# proto.net
KiCad netlist of a schematic drawn in EAGLE
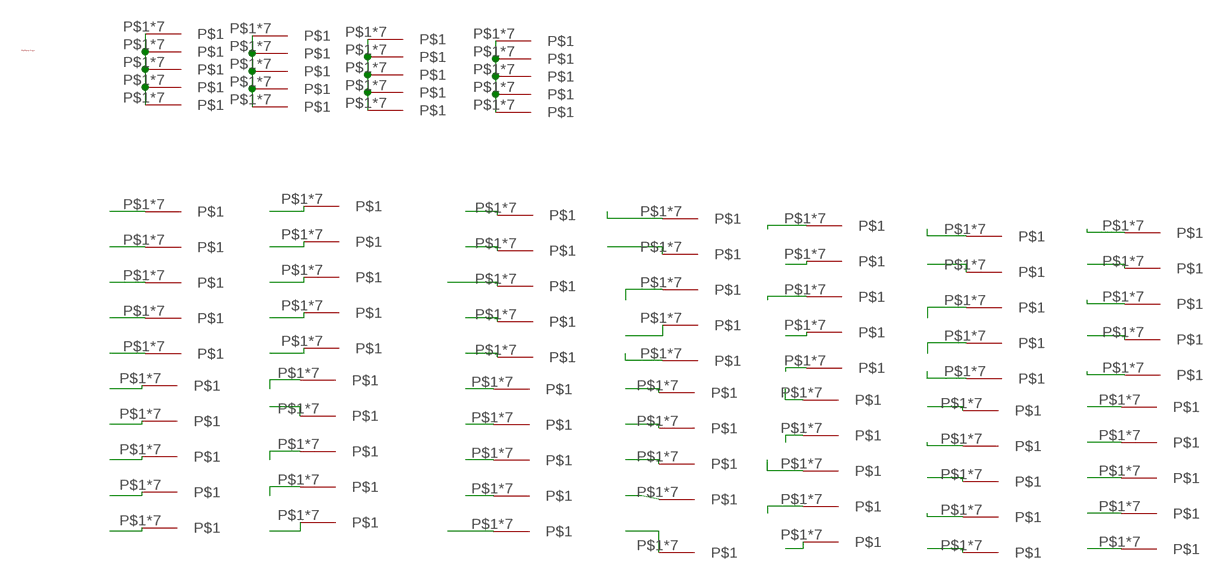
[diagram p0: schematic, sheet 1]

(export (version "E")
  (design (tool "Eeschema 10.0.6"))
  (components
    (comp (ref "U$1")
      (value "LOGO_HACKHEIM")
      (footprint "eagle-import:LOGO_HACKHEIM")
      (libsource (lib "eagle-import") (part "LOGO_HACKHEIM"))
    )
    (comp (ref "U$4")
      (value "PROTO_PAD")
      (footprint "eagle-import:PROTO_PAD")
      (libsource (lib "eagle-import") (part "PROTO_PAD"))
    )
    (comp (ref "U$5")
      (value "PROTO_PAD")
      (footprint "eagle-import:PROTO_PAD")
      (libsource (lib "eagle-import") (part "PROTO_PAD"))
    )
    (comp (ref "U$6")
      (value "PROTO_PAD")
      (footprint "eagle-import:PROTO_PAD")
      (libsource (lib "eagle-import") (part "PROTO_PAD"))
    )
    (comp (ref "U$7")
      (value "PROTO_PAD")
      (footprint "eagle-import:PROTO_PAD")
      (libsource (lib "eagle-import") (part "PROTO_PAD"))
    )
    (comp (ref "U$8")
      (value "PROTO_PAD")
      (footprint "eagle-import:PROTO_PAD")
      (libsource (lib "eagle-import") (part "PROTO_PAD"))
    )
    (comp (ref "U$9")
      (value "PROTO_PAD")
      (footprint "eagle-import:PROTO_PAD")
      (libsource (lib "eagle-import") (part "PROTO_PAD"))
    )
    (comp (ref "U$10")
      (value "PROTO_PAD")
      (footprint "eagle-import:PROTO_PAD")
      (libsource (lib "eagle-import") (part "PROTO_PAD"))
    )
    (comp (ref "U$11")
      (value "PROTO_PAD")
      (footprint "eagle-import:PROTO_PAD")
      (libsource (lib "eagle-import") (part "PROTO_PAD"))
    )
    (comp (ref "U$12")
      (value "PROTO_PAD")
      (footprint "eagle-import:PROTO_PAD")
      (libsource (lib "eagle-import") (part "PROTO_PAD"))
    )
    (comp (ref "U$13")
      (value "PROTO_PAD")
      (footprint "eagle-import:PROTO_PAD")
      (libsource (lib "eagle-import") (part "PROTO_PAD"))
    )
    (comp (ref "U$14")
      (value "PROTO_PAD")
      (footprint "eagle-import:PROTO_PAD")
      (libsource (lib "eagle-import") (part "PROTO_PAD"))
    )
    (comp (ref "U$15")
      (value "PROTO_PAD")
      (footprint "eagle-import:PROTO_PAD")
      (libsource (lib "eagle-import") (part "PROTO_PAD"))
    )
    (comp (ref "U$16")
      (value "PROTO_PAD")
      (footprint "eagle-import:PROTO_PAD")
      (libsource (lib "eagle-import") (part "PROTO_PAD"))
    )
    (comp (ref "U$17")
      (value "PROTO_PAD")
      (footprint "eagle-import:PROTO_PAD")
      (libsource (lib "eagle-import") (part "PROTO_PAD"))
    )
    (comp (ref "U$18")
      (value "PROTO_PAD")
      (footprint "eagle-import:PROTO_PAD")
      (libsource (lib "eagle-import") (part "PROTO_PAD"))
    )
    (comp (ref "U$19")
      (value "PROTO_PAD")
      (footprint "eagle-import:PROTO_PAD")
      (libsource (lib "eagle-import") (part "PROTO_PAD"))
    )
    (comp (ref "U$20")
      (value "PROTO_PAD")
      (footprint "eagle-import:PROTO_PAD")
      (libsource (lib "eagle-import") (part "PROTO_PAD"))
    )
    (comp (ref "U$21")
      (value "PROTO_PAD")
      (footprint "eagle-import:PROTO_PAD")
      (libsource (lib "eagle-import") (part "PROTO_PAD"))
    )
    (comp (ref "U$22")
      (value "PROTO_PAD")
      (footprint "eagle-import:PROTO_PAD")
      (libsource (lib "eagle-import") (part "PROTO_PAD"))
    )
    (comp (ref "U$23")
      (value "PROTO_PAD")
      (footprint "eagle-import:PROTO_PAD")
      (libsource (lib "eagle-import") (part "PROTO_PAD"))
    )
    (comp (ref "U$24")
      (value "PROTO_PAD")
      (footprint "eagle-import:PROTO_PAD")
      (libsource (lib "eagle-import") (part "PROTO_PAD"))
    )
    (comp (ref "U$25")
      (value "PROTO_PAD")
      (footprint "eagle-import:PROTO_PAD")
      (libsource (lib "eagle-import") (part "PROTO_PAD"))
    )
    (comp (ref "U$26")
      (value "PROTO_PAD")
      (footprint "eagle-import:PROTO_PAD")
      (libsource (lib "eagle-import") (part "PROTO_PAD"))
    )
    (comp (ref "U$27")
      (value "PROTO_PAD")
      (footprint "eagle-import:PROTO_PAD")
      (libsource (lib "eagle-import") (part "PROTO_PAD"))
    )
    (comp (ref "U$28")
      (value "PROTO_PAD")
      (footprint "eagle-import:PROTO_PAD")
      (libsource (lib "eagle-import") (part "PROTO_PAD"))
    )
    (comp (ref "U$29")
      (value "PROTO_PAD")
      (footprint "eagle-import:PROTO_PAD")
      (libsource (lib "eagle-import") (part "PROTO_PAD"))
    )
    (comp (ref "U$30")
      (value "PROTO_PAD")
      (footprint "eagle-import:PROTO_PAD")
      (libsource (lib "eagle-import") (part "PROTO_PAD"))
    )
    (comp (ref "U$31")
      (value "PROTO_PAD")
      (footprint "eagle-import:PROTO_PAD")
      (libsource (lib "eagle-import") (part "PROTO_PAD"))
    )
    (comp (ref "U$32")
      (value "PROTO_PAD")
      (footprint "eagle-import:PROTO_PAD")
      (libsource (lib "eagle-import") (part "PROTO_PAD"))
    )
    (comp (ref "U$33")
      (value "PROTO_PAD")
      (footprint "eagle-import:PROTO_PAD")
      (libsource (lib "eagle-import") (part "PROTO_PAD"))
    )
    (comp (ref "U$34")
      (value "PROTO_PAD")
      (footprint "eagle-import:PROTO_PAD")
      (libsource (lib "eagle-import") (part "PROTO_PAD"))
    )
    (comp (ref "U$35")
      (value "PROTO_PAD")
      (footprint "eagle-import:PROTO_PAD")
      (libsource (lib "eagle-import") (part "PROTO_PAD"))
    )
    (comp (ref "U$36")
      (value "PROTO_PAD")
      (footprint "eagle-import:PROTO_PAD")
      (libsource (lib "eagle-import") (part "PROTO_PAD"))
    )
    (comp (ref "U$37")
      (value "PROTO_PAD")
      (footprint "eagle-import:PROTO_PAD")
      (libsource (lib "eagle-import") (part "PROTO_PAD"))
    )
    (comp (ref "U$38")
      (value "PROTO_PAD")
      (footprint "eagle-import:PROTO_PAD")
      (libsource (lib "eagle-import") (part "PROTO_PAD"))
    )
    (comp (ref "U$39")
      (value "PROTO_PAD")
      (footprint "eagle-import:PROTO_PAD")
      (libsource (lib "eagle-import") (part "PROTO_PAD"))
    )
    (comp (ref "U$40")
      (value "PROTO_PAD")
      (footprint "eagle-import:PROTO_PAD")
      (libsource (lib "eagle-import") (part "PROTO_PAD"))
    )
    (comp (ref "U$41")
      (value "PROTO_PAD")
      (footprint "eagle-import:PROTO_PAD")
      (libsource (lib "eagle-import") (part "PROTO_PAD"))
    )
    (comp (ref "U$42")
      (value "PROTO_PAD")
      (footprint "eagle-import:PROTO_PAD")
      (libsource (lib "eagle-import") (part "PROTO_PAD"))
    )
    (comp (ref "U$43")
      (value "PROTO_PAD")
      (footprint "eagle-import:PROTO_PAD")
      (libsource (lib "eagle-import") (part "PROTO_PAD"))
    )
    (comp (ref "U$44")
      (value "PROTO_PAD")
      (footprint "eagle-import:PROTO_PAD")
      (libsource (lib "eagle-import") (part "PROTO_PAD"))
    )
    (comp (ref "U$45")
      (value "PROTO_PAD")
      (footprint "eagle-import:PROTO_PAD")
      (libsource (lib "eagle-import") (part "PROTO_PAD"))
    )
    (comp (ref "U$46")
      (value "PROTO_PAD")
      (footprint "eagle-import:PROTO_PAD")
      (libsource (lib "eagle-import") (part "PROTO_PAD"))
    )
    (comp (ref "U$47")
      (value "PROTO_PAD")
      (footprint "eagle-import:PROTO_PAD")
      (libsource (lib "eagle-import") (part "PROTO_PAD"))
    )
    (comp (ref "U$48")
      (value "PROTO_PAD")
      (footprint "eagle-import:PROTO_PAD")
      (libsource (lib "eagle-import") (part "PROTO_PAD"))
    )
    (comp (ref "U$49")
      (value "PROTO_PAD")
      (footprint "eagle-import:PROTO_PAD")
      (libsource (lib "eagle-import") (part "PROTO_PAD"))
    )
    (comp (ref "U$50")
      (value "PROTO_PAD")
      (footprint "eagle-import:PROTO_PAD")
      (libsource (lib "eagle-import") (part "PROTO_PAD"))
    )
    (comp (ref "U$51")
      (value "PROTO_PAD")
      (footprint "eagle-import:PROTO_PAD")
      (libsource (lib "eagle-import") (part "PROTO_PAD"))
    )
    (comp (ref "U$52")
      (value "PROTO_PAD")
      (footprint "eagle-import:PROTO_PAD")
      (libsource (lib "eagle-import") (part "PROTO_PAD"))
    )
    (comp (ref "U$53")
      (value "PROTO_PAD")
      (footprint "eagle-import:PROTO_PAD")
      (libsource (lib "eagle-import") (part "PROTO_PAD"))
    )
    (comp (ref "U$54")
      (value "PROTO_PAD")
      (footprint "eagle-import:PROTO_PAD")
      (libsource (lib "eagle-import") (part "PROTO_PAD"))
    )
    (comp (ref "U$55")
      (value "PROTO_PAD")
      (footprint "eagle-import:PROTO_PAD")
      (libsource (lib "eagle-import") (part "PROTO_PAD"))
    )
    (comp (ref "U$56")
      (value "PROTO_PAD")
      (footprint "eagle-import:PROTO_PAD")
      (libsource (lib "eagle-import") (part "PROTO_PAD"))
    )
    (comp (ref "U$57")
      (value "PROTO_PAD")
      (footprint "eagle-import:PROTO_PAD")
      (libsource (lib "eagle-import") (part "PROTO_PAD"))
    )
    (comp (ref "U$58")
      (value "PROTO_PAD")
      (footprint "eagle-import:PROTO_PAD")
      (libsource (lib "eagle-import") (part "PROTO_PAD"))
    )
    (comp (ref "U$59")
      (value "PROTO_PAD")
      (footprint "eagle-import:PROTO_PAD")
      (libsource (lib "eagle-import") (part "PROTO_PAD"))
    )
    (comp (ref "U$60")
      (value "PROTO_PAD")
      (footprint "eagle-import:PROTO_PAD")
      (libsource (lib "eagle-import") (part "PROTO_PAD"))
    )
    (comp (ref "U$61")
      (value "PROTO_PAD")
      (footprint "eagle-import:PROTO_PAD")
      (libsource (lib "eagle-import") (part "PROTO_PAD"))
    )
    (comp (ref "U$62")
      (value "PROTO_PAD")
      (footprint "eagle-import:PROTO_PAD")
      (libsource (lib "eagle-import") (part "PROTO_PAD"))
    )
    (comp (ref "U$63")
      (value "PROTO_PAD")
      (footprint "eagle-import:PROTO_PAD")
      (libsource (lib "eagle-import") (part "PROTO_PAD"))
    )
    (comp (ref "U$64")
      (value "PROTO_PAD")
      (footprint "eagle-import:PROTO_PAD")
      (libsource (lib "eagle-import") (part "PROTO_PAD"))
    )
    (comp (ref "U$65")
      (value "PROTO_PAD")
      (footprint "eagle-import:PROTO_PAD")
      (libsource (lib "eagle-import") (part "PROTO_PAD"))
    )
    (comp (ref "U$66")
      (value "PROTO_PAD")
      (footprint "eagle-import:PROTO_PAD")
      (libsource (lib "eagle-import") (part "PROTO_PAD"))
    )
    (comp (ref "U$67")
      (value "PROTO_PAD")
      (footprint "eagle-import:PROTO_PAD")
      (libsource (lib "eagle-import") (part "PROTO_PAD"))
    )
    (comp (ref "U$68")
      (value "PROTO_PAD")
      (footprint "eagle-import:PROTO_PAD")
      (libsource (lib "eagle-import") (part "PROTO_PAD"))
    )
    (comp (ref "U$69")
      (value "PROTO_PAD")
      (footprint "eagle-import:PROTO_PAD")
      (libsource (lib "eagle-import") (part "PROTO_PAD"))
    )
    (comp (ref "U$70")
      (value "PROTO_PAD")
      (footprint "eagle-import:PROTO_PAD")
      (libsource (lib "eagle-import") (part "PROTO_PAD"))
    )
    (comp (ref "U$71")
      (value "PROTO_PAD")
      (footprint "eagle-import:PROTO_PAD")
      (libsource (lib "eagle-import") (part "PROTO_PAD"))
    )
    (comp (ref "U$72")
      (value "PROTO_PAD")
      (footprint "eagle-import:PROTO_PAD")
      (libsource (lib "eagle-import") (part "PROTO_PAD"))
    )
    (comp (ref "U$73")
      (value "PROTO_PAD")
      (footprint "eagle-import:PROTO_PAD")
      (libsource (lib "eagle-import") (part "PROTO_PAD"))
    )
    (comp (ref "U$74")
      (value "PROTO_PAD")
      (footprint "eagle-import:PROTO_PAD")
      (libsource (lib "eagle-import") (part "PROTO_PAD"))
    )
    (comp (ref "U$75")
      (value "PROTO_PAD")
      (footprint "eagle-import:PROTO_PAD")
      (libsource (lib "eagle-import") (part "PROTO_PAD"))
    )
    (comp (ref "U$76")
      (value "PROTO_PAD")
      (footprint "eagle-import:PROTO_PAD")
      (libsource (lib "eagle-import") (part "PROTO_PAD"))
    )
    (comp (ref "U$77")
      (value "PROTO_PAD")
      (footprint "eagle-import:PROTO_PAD")
      (libsource (lib "eagle-import") (part "PROTO_PAD"))
    )
    (comp (ref "U$78")
      (value "PROTO_PAD")
      (footprint "eagle-import:PROTO_PAD")
      (libsource (lib "eagle-import") (part "PROTO_PAD"))
    )
    (comp (ref "U$79")
      (value "PROTO_PAD")
      (footprint "eagle-import:PROTO_PAD")
      (libsource (lib "eagle-import") (part "PROTO_PAD"))
    )
    (comp (ref "U$80")
      (value "PROTO_PAD")
      (footprint "eagle-import:PROTO_PAD")
      (libsource (lib "eagle-import") (part "PROTO_PAD"))
    )
    (comp (ref "U$81")
      (value "PROTO_PAD")
      (footprint "eagle-import:PROTO_PAD")
      (libsource (lib "eagle-import") (part "PROTO_PAD"))
    )
    (comp (ref "U$82")
      (value "PROTO_PAD")
      (footprint "eagle-import:PROTO_PAD")
      (libsource (lib "eagle-import") (part "PROTO_PAD"))
    )
    (comp (ref "U$83")
      (value "PROTO_PAD")
      (footprint "eagle-import:PROTO_PAD")
      (libsource (lib "eagle-import") (part "PROTO_PAD"))
    )
    (comp (ref "U$84")
      (value "PROTO_PAD")
      (footprint "eagle-import:PROTO_PAD")
      (libsource (lib "eagle-import") (part "PROTO_PAD"))
    )
    (comp (ref "U$85")
      (value "PROTO_PAD")
      (footprint "eagle-import:PROTO_PAD")
      (libsource (lib "eagle-import") (part "PROTO_PAD"))
    )
    (comp (ref "U$86")
      (value "PROTO_PAD")
      (footprint "eagle-import:PROTO_PAD")
      (libsource (lib "eagle-import") (part "PROTO_PAD"))
    )
    (comp (ref "U$87")
      (value "PROTO_PAD")
      (footprint "eagle-import:PROTO_PAD")
      (libsource (lib "eagle-import") (part "PROTO_PAD"))
    )
    (comp (ref "U$88")
      (value "PROTO_PAD")
      (footprint "eagle-import:PROTO_PAD")
      (libsource (lib "eagle-import") (part "PROTO_PAD"))
    )
    (comp (ref "U$89")
      (value "PROTO_PAD")
      (footprint "eagle-import:PROTO_PAD")
      (libsource (lib "eagle-import") (part "PROTO_PAD"))
    )
    (comp (ref "U$90")
      (value "PROTO_PAD")
      (footprint "eagle-import:PROTO_PAD")
      (libsource (lib "eagle-import") (part "PROTO_PAD"))
    )
    (comp (ref "U$91")
      (value "PROTO_PAD")
      (footprint "eagle-import:PROTO_PAD")
      (libsource (lib "eagle-import") (part "PROTO_PAD"))
    )
    (comp (ref "U$92")
      (value "PROTO_PAD")
      (footprint "eagle-import:PROTO_PAD")
      (libsource (lib "eagle-import") (part "PROTO_PAD"))
    )
    (comp (ref "U$93")
      (value "PROTO_PAD")
      (footprint "eagle-import:PROTO_PAD")
      (libsource (lib "eagle-import") (part "PROTO_PAD"))
    )
  )
  (nets
    (net (code "1") (name "Net-(U$4-P$1-PadP$2)") (class "Default")
      (node (ref "U$4") (pin "P$1") (pinfunction "P$1_P$1") (pintype "bidirectional"))
      (node (ref "U$4") (pin "P$2") (pinfunction "P$1_P$2") (pintype "bidirectional"))
      (node (ref "U$4") (pin "P$3") (pinfunction "P$1_P$3") (pintype "bidirectional"))
      (node (ref "U$4") (pin "P$4") (pinfunction "P$1_P$4") (pintype "bidirectional"))
      (node (ref "U$4") (pin "P$5") (pinfunction "P$1_P$5") (pintype "bidirectional"))
      (node (ref "U$4") (pin "P$6") (pinfunction "P$1_P$6") (pintype "bidirectional"))
      (node (ref "U$4") (pin "P$7") (pinfunction "P$1_P$7") (pintype "bidirectional"))
      (node (ref "U$5") (pin "P$1") (pinfunction "P$1_P$1") (pintype "bidirectional"))
      (node (ref "U$5") (pin "P$2") (pinfunction "P$1_P$2") (pintype "bidirectional"))
      (node (ref "U$5") (pin "P$3") (pinfunction "P$1_P$3") (pintype "bidirectional"))
      (node (ref "U$5") (pin "P$4") (pinfunction "P$1_P$4") (pintype "bidirectional"))
      (node (ref "U$5") (pin "P$5") (pinfunction "P$1_P$5") (pintype "bidirectional"))
      (node (ref "U$5") (pin "P$6") (pinfunction "P$1_P$6") (pintype "bidirectional"))
      (node (ref "U$5") (pin "P$7") (pinfunction "P$1_P$7") (pintype "bidirectional"))
      (node (ref "U$6") (pin "P$1") (pinfunction "P$1_P$1") (pintype "bidirectional"))
      (node (ref "U$6") (pin "P$2") (pinfunction "P$1_P$2") (pintype "bidirectional"))
      (node (ref "U$6") (pin "P$3") (pinfunction "P$1_P$3") (pintype "bidirectional"))
      (node (ref "U$6") (pin "P$4") (pinfunction "P$1_P$4") (pintype "bidirectional"))
      (node (ref "U$6") (pin "P$5") (pinfunction "P$1_P$5") (pintype "bidirectional"))
      (node (ref "U$6") (pin "P$6") (pinfunction "P$1_P$6") (pintype "bidirectional"))
      (node (ref "U$6") (pin "P$7") (pinfunction "P$1_P$7") (pintype "bidirectional"))
      (node (ref "U$7") (pin "P$1") (pinfunction "P$1_P$1") (pintype "bidirectional"))
      (node (ref "U$7") (pin "P$2") (pinfunction "P$1_P$2") (pintype "bidirectional"))
      (node (ref "U$7") (pin "P$3") (pinfunction "P$1_P$3") (pintype "bidirectional"))
      (node (ref "U$7") (pin "P$4") (pinfunction "P$1_P$4") (pintype "bidirectional"))
      (node (ref "U$7") (pin "P$5") (pinfunction "P$1_P$5") (pintype "bidirectional"))
      (node (ref "U$7") (pin "P$6") (pinfunction "P$1_P$6") (pintype "bidirectional"))
      (node (ref "U$7") (pin "P$7") (pinfunction "P$1_P$7") (pintype "bidirectional"))
      (node (ref "U$8") (pin "P$1") (pinfunction "P$1_P$1") (pintype "bidirectional"))
      (node (ref "U$8") (pin "P$2") (pinfunction "P$1_P$2") (pintype "bidirectional"))
      (node (ref "U$8") (pin "P$3") (pinfunction "P$1_P$3") (pintype "bidirectional"))
      (node (ref "U$8") (pin "P$4") (pinfunction "P$1_P$4") (pintype "bidirectional"))
      (node (ref "U$8") (pin "P$5") (pinfunction "P$1_P$5") (pintype "bidirectional"))
      (node (ref "U$8") (pin "P$6") (pinfunction "P$1_P$6") (pintype "bidirectional"))
      (node (ref "U$8") (pin "P$7") (pinfunction "P$1_P$7") (pintype "bidirectional"))
    )
    (net (code "2") (name "Net-(U$10-P$1-PadP$2)") (class "Default")
      (node (ref "U$10") (pin "P$1") (pinfunction "P$1_P$1") (pintype "bidirectional"))
      (node (ref "U$10") (pin "P$2") (pinfunction "P$1_P$2") (pintype "bidirectional"))
      (node (ref "U$10") (pin "P$3") (pinfunction "P$1_P$3") (pintype "bidirectional"))
      (node (ref "U$10") (pin "P$4") (pinfunction "P$1_P$4") (pintype "bidirectional"))
      (node (ref "U$10") (pin "P$5") (pinfunction "P$1_P$5") (pintype "bidirectional"))
      (node (ref "U$10") (pin "P$6") (pinfunction "P$1_P$6") (pintype "bidirectional"))
      (node (ref "U$10") (pin "P$7") (pinfunction "P$1_P$7") (pintype "bidirectional"))
      (node (ref "U$11") (pin "P$1") (pinfunction "P$1_P$1") (pintype "bidirectional"))
      (node (ref "U$11") (pin "P$2") (pinfunction "P$1_P$2") (pintype "bidirectional"))
      (node (ref "U$11") (pin "P$3") (pinfunction "P$1_P$3") (pintype "bidirectional"))
      (node (ref "U$11") (pin "P$4") (pinfunction "P$1_P$4") (pintype "bidirectional"))
      (node (ref "U$11") (pin "P$5") (pinfunction "P$1_P$5") (pintype "bidirectional"))
      (node (ref "U$11") (pin "P$6") (pinfunction "P$1_P$6") (pintype "bidirectional"))
      (node (ref "U$11") (pin "P$7") (pinfunction "P$1_P$7") (pintype "bidirectional"))
      (node (ref "U$12") (pin "P$1") (pinfunction "P$1_P$1") (pintype "bidirectional"))
      (node (ref "U$12") (pin "P$2") (pinfunction "P$1_P$2") (pintype "bidirectional"))
      (node (ref "U$12") (pin "P$3") (pinfunction "P$1_P$3") (pintype "bidirectional"))
      (node (ref "U$12") (pin "P$4") (pinfunction "P$1_P$4") (pintype "bidirectional"))
      (node (ref "U$12") (pin "P$5") (pinfunction "P$1_P$5") (pintype "bidirectional"))
      (node (ref "U$12") (pin "P$6") (pinfunction "P$1_P$6") (pintype "bidirectional"))
      (node (ref "U$12") (pin "P$7") (pinfunction "P$1_P$7") (pintype "bidirectional"))
      (node (ref "U$13") (pin "P$1") (pinfunction "P$1_P$1") (pintype "bidirectional"))
      (node (ref "U$13") (pin "P$2") (pinfunction "P$1_P$2") (pintype "bidirectional"))
      (node (ref "U$13") (pin "P$3") (pinfunction "P$1_P$3") (pintype "bidirectional"))
      (node (ref "U$13") (pin "P$4") (pinfunction "P$1_P$4") (pintype "bidirectional"))
      (node (ref "U$13") (pin "P$5") (pinfunction "P$1_P$5") (pintype "bidirectional"))
      (node (ref "U$13") (pin "P$6") (pinfunction "P$1_P$6") (pintype "bidirectional"))
      (node (ref "U$13") (pin "P$7") (pinfunction "P$1_P$7") (pintype "bidirectional"))
      (node (ref "U$9") (pin "P$1") (pinfunction "P$1_P$1") (pintype "bidirectional"))
      (node (ref "U$9") (pin "P$2") (pinfunction "P$1_P$2") (pintype "bidirectional"))
      (node (ref "U$9") (pin "P$3") (pinfunction "P$1_P$3") (pintype "bidirectional"))
      (node (ref "U$9") (pin "P$4") (pinfunction "P$1_P$4") (pintype "bidirectional"))
      (node (ref "U$9") (pin "P$5") (pinfunction "P$1_P$5") (pintype "bidirectional"))
      (node (ref "U$9") (pin "P$6") (pinfunction "P$1_P$6") (pintype "bidirectional"))
      (node (ref "U$9") (pin "P$7") (pinfunction "P$1_P$7") (pintype "bidirectional"))
    )
    (net (code "3") (name "Net-(U$14-P$1-PadP$2)") (class "Default")
      (node (ref "U$14") (pin "P$1") (pinfunction "P$1_P$1") (pintype "bidirectional"))
      (node (ref "U$14") (pin "P$2") (pinfunction "P$1_P$2") (pintype "bidirectional"))
      (node (ref "U$14") (pin "P$3") (pinfunction "P$1_P$3") (pintype "bidirectional"))
      (node (ref "U$14") (pin "P$4") (pinfunction "P$1_P$4") (pintype "bidirectional"))
      (node (ref "U$14") (pin "P$5") (pinfunction "P$1_P$5") (pintype "bidirectional"))
      (node (ref "U$14") (pin "P$6") (pinfunction "P$1_P$6") (pintype "bidirectional"))
      (node (ref "U$14") (pin "P$7") (pinfunction "P$1_P$7") (pintype "bidirectional"))
    )
    (net (code "4") (name "Net-(U$15-P$1-PadP$2)") (class "Default")
      (node (ref "U$15") (pin "P$1") (pinfunction "P$1_P$1") (pintype "bidirectional"))
      (node (ref "U$15") (pin "P$2") (pinfunction "P$1_P$2") (pintype "bidirectional"))
      (node (ref "U$15") (pin "P$3") (pinfunction "P$1_P$3") (pintype "bidirectional"))
      (node (ref "U$15") (pin "P$4") (pinfunction "P$1_P$4") (pintype "bidirectional"))
      (node (ref "U$15") (pin "P$5") (pinfunction "P$1_P$5") (pintype "bidirectional"))
      (node (ref "U$15") (pin "P$6") (pinfunction "P$1_P$6") (pintype "bidirectional"))
      (node (ref "U$15") (pin "P$7") (pinfunction "P$1_P$7") (pintype "bidirectional"))
    )
    (net (code "5") (name "Net-(U$16-P$1-PadP$2)") (class "Default")
      (node (ref "U$16") (pin "P$1") (pinfunction "P$1_P$1") (pintype "bidirectional"))
      (node (ref "U$16") (pin "P$2") (pinfunction "P$1_P$2") (pintype "bidirectional"))
      (node (ref "U$16") (pin "P$3") (pinfunction "P$1_P$3") (pintype "bidirectional"))
      (node (ref "U$16") (pin "P$4") (pinfunction "P$1_P$4") (pintype "bidirectional"))
      (node (ref "U$16") (pin "P$5") (pinfunction "P$1_P$5") (pintype "bidirectional"))
      (node (ref "U$16") (pin "P$6") (pinfunction "P$1_P$6") (pintype "bidirectional"))
      (node (ref "U$16") (pin "P$7") (pinfunction "P$1_P$7") (pintype "bidirectional"))
    )
    (net (code "6") (name "Net-(U$17-P$1-PadP$2)") (class "Default")
      (node (ref "U$17") (pin "P$1") (pinfunction "P$1_P$1") (pintype "bidirectional"))
      (node (ref "U$17") (pin "P$2") (pinfunction "P$1_P$2") (pintype "bidirectional"))
      (node (ref "U$17") (pin "P$3") (pinfunction "P$1_P$3") (pintype "bidirectional"))
      (node (ref "U$17") (pin "P$4") (pinfunction "P$1_P$4") (pintype "bidirectional"))
      (node (ref "U$17") (pin "P$5") (pinfunction "P$1_P$5") (pintype "bidirectional"))
      (node (ref "U$17") (pin "P$6") (pinfunction "P$1_P$6") (pintype "bidirectional"))
      (node (ref "U$17") (pin "P$7") (pinfunction "P$1_P$7") (pintype "bidirectional"))
    )
    (net (code "7") (name "Net-(U$18-P$1-PadP$2)") (class "Default")
      (node (ref "U$18") (pin "P$1") (pinfunction "P$1_P$1") (pintype "bidirectional"))
      (node (ref "U$18") (pin "P$2") (pinfunction "P$1_P$2") (pintype "bidirectional"))
      (node (ref "U$18") (pin "P$3") (pinfunction "P$1_P$3") (pintype "bidirectional"))
      (node (ref "U$18") (pin "P$4") (pinfunction "P$1_P$4") (pintype "bidirectional"))
      (node (ref "U$18") (pin "P$5") (pinfunction "P$1_P$5") (pintype "bidirectional"))
      (node (ref "U$18") (pin "P$6") (pinfunction "P$1_P$6") (pintype "bidirectional"))
      (node (ref "U$18") (pin "P$7") (pinfunction "P$1_P$7") (pintype "bidirectional"))
    )
    (net (code "8") (name "Net-(U$19-P$1-PadP$2)") (class "Default")
      (node (ref "U$19") (pin "P$1") (pinfunction "P$1_P$1") (pintype "bidirectional"))
      (node (ref "U$19") (pin "P$2") (pinfunction "P$1_P$2") (pintype "bidirectional"))
      (node (ref "U$19") (pin "P$3") (pinfunction "P$1_P$3") (pintype "bidirectional"))
      (node (ref "U$19") (pin "P$4") (pinfunction "P$1_P$4") (pintype "bidirectional"))
      (node (ref "U$19") (pin "P$5") (pinfunction "P$1_P$5") (pintype "bidirectional"))
      (node (ref "U$19") (pin "P$6") (pinfunction "P$1_P$6") (pintype "bidirectional"))
      (node (ref "U$19") (pin "P$7") (pinfunction "P$1_P$7") (pintype "bidirectional"))
    )
    (net (code "9") (name "Net-(U$20-P$1-PadP$2)") (class "Default")
      (node (ref "U$20") (pin "P$1") (pinfunction "P$1_P$1") (pintype "bidirectional"))
      (node (ref "U$20") (pin "P$2") (pinfunction "P$1_P$2") (pintype "bidirectional"))
      (node (ref "U$20") (pin "P$3") (pinfunction "P$1_P$3") (pintype "bidirectional"))
      (node (ref "U$20") (pin "P$4") (pinfunction "P$1_P$4") (pintype "bidirectional"))
      (node (ref "U$20") (pin "P$5") (pinfunction "P$1_P$5") (pintype "bidirectional"))
      (node (ref "U$20") (pin "P$6") (pinfunction "P$1_P$6") (pintype "bidirectional"))
      (node (ref "U$20") (pin "P$7") (pinfunction "P$1_P$7") (pintype "bidirectional"))
    )
    (net (code "10") (name "Net-(U$21-P$1-PadP$2)") (class "Default")
      (node (ref "U$21") (pin "P$1") (pinfunction "P$1_P$1") (pintype "bidirectional"))
      (node (ref "U$21") (pin "P$2") (pinfunction "P$1_P$2") (pintype "bidirectional"))
      (node (ref "U$21") (pin "P$3") (pinfunction "P$1_P$3") (pintype "bidirectional"))
      (node (ref "U$21") (pin "P$4") (pinfunction "P$1_P$4") (pintype "bidirectional"))
      (node (ref "U$21") (pin "P$5") (pinfunction "P$1_P$5") (pintype "bidirectional"))
      (node (ref "U$21") (pin "P$6") (pinfunction "P$1_P$6") (pintype "bidirectional"))
      (node (ref "U$21") (pin "P$7") (pinfunction "P$1_P$7") (pintype "bidirectional"))
    )
    (net (code "11") (name "Net-(U$22-P$1-PadP$2)") (class "Default")
      (node (ref "U$22") (pin "P$1") (pinfunction "P$1_P$1") (pintype "bidirectional"))
      (node (ref "U$22") (pin "P$2") (pinfunction "P$1_P$2") (pintype "bidirectional"))
      (node (ref "U$22") (pin "P$3") (pinfunction "P$1_P$3") (pintype "bidirectional"))
      (node (ref "U$22") (pin "P$4") (pinfunction "P$1_P$4") (pintype "bidirectional"))
      (node (ref "U$22") (pin "P$5") (pinfunction "P$1_P$5") (pintype "bidirectional"))
      (node (ref "U$22") (pin "P$6") (pinfunction "P$1_P$6") (pintype "bidirectional"))
      (node (ref "U$22") (pin "P$7") (pinfunction "P$1_P$7") (pintype "bidirectional"))
    )
    (net (code "12") (name "Net-(U$23-P$1-PadP$2)") (class "Default")
      (node (ref "U$23") (pin "P$1") (pinfunction "P$1_P$1") (pintype "bidirectional"))
      (node (ref "U$23") (pin "P$2") (pinfunction "P$1_P$2") (pintype "bidirectional"))
      (node (ref "U$23") (pin "P$3") (pinfunction "P$1_P$3") (pintype "bidirectional"))
      (node (ref "U$23") (pin "P$4") (pinfunction "P$1_P$4") (pintype "bidirectional"))
      (node (ref "U$23") (pin "P$5") (pinfunction "P$1_P$5") (pintype "bidirectional"))
      (node (ref "U$23") (pin "P$6") (pinfunction "P$1_P$6") (pintype "bidirectional"))
      (node (ref "U$23") (pin "P$7") (pinfunction "P$1_P$7") (pintype "bidirectional"))
    )
    (net (code "13") (name "Net-(U$24-P$1-PadP$2)") (class "Default")
      (node (ref "U$24") (pin "P$1") (pinfunction "P$1_P$1") (pintype "bidirectional"))
      (node (ref "U$24") (pin "P$2") (pinfunction "P$1_P$2") (pintype "bidirectional"))
      (node (ref "U$24") (pin "P$3") (pinfunction "P$1_P$3") (pintype "bidirectional"))
      (node (ref "U$24") (pin "P$4") (pinfunction "P$1_P$4") (pintype "bidirectional"))
      (node (ref "U$24") (pin "P$5") (pinfunction "P$1_P$5") (pintype "bidirectional"))
      (node (ref "U$24") (pin "P$6") (pinfunction "P$1_P$6") (pintype "bidirectional"))
      (node (ref "U$24") (pin "P$7") (pinfunction "P$1_P$7") (pintype "bidirectional"))
      (node (ref "U$25") (pin "P$1") (pinfunction "P$1_P$1") (pintype "bidirectional"))
      (node (ref "U$25") (pin "P$2") (pinfunction "P$1_P$2") (pintype "bidirectional"))
      (node (ref "U$25") (pin "P$3") (pinfunction "P$1_P$3") (pintype "bidirectional"))
      (node (ref "U$25") (pin "P$4") (pinfunction "P$1_P$4") (pintype "bidirectional"))
      (node (ref "U$25") (pin "P$5") (pinfunction "P$1_P$5") (pintype "bidirectional"))
      (node (ref "U$25") (pin "P$6") (pinfunction "P$1_P$6") (pintype "bidirectional"))
      (node (ref "U$25") (pin "P$7") (pinfunction "P$1_P$7") (pintype "bidirectional"))
      (node (ref "U$26") (pin "P$1") (pinfunction "P$1_P$1") (pintype "bidirectional"))
      (node (ref "U$26") (pin "P$2") (pinfunction "P$1_P$2") (pintype "bidirectional"))
      (node (ref "U$26") (pin "P$3") (pinfunction "P$1_P$3") (pintype "bidirectional"))
      (node (ref "U$26") (pin "P$4") (pinfunction "P$1_P$4") (pintype "bidirectional"))
      (node (ref "U$26") (pin "P$5") (pinfunction "P$1_P$5") (pintype "bidirectional"))
      (node (ref "U$26") (pin "P$6") (pinfunction "P$1_P$6") (pintype "bidirectional"))
      (node (ref "U$26") (pin "P$7") (pinfunction "P$1_P$7") (pintype "bidirectional"))
      (node (ref "U$27") (pin "P$1") (pinfunction "P$1_P$1") (pintype "bidirectional"))
      (node (ref "U$27") (pin "P$2") (pinfunction "P$1_P$2") (pintype "bidirectional"))
      (node (ref "U$27") (pin "P$3") (pinfunction "P$1_P$3") (pintype "bidirectional"))
      (node (ref "U$27") (pin "P$4") (pinfunction "P$1_P$4") (pintype "bidirectional"))
      (node (ref "U$27") (pin "P$5") (pinfunction "P$1_P$5") (pintype "bidirectional"))
      (node (ref "U$27") (pin "P$6") (pinfunction "P$1_P$6") (pintype "bidirectional"))
      (node (ref "U$27") (pin "P$7") (pinfunction "P$1_P$7") (pintype "bidirectional"))
      (node (ref "U$28") (pin "P$1") (pinfunction "P$1_P$1") (pintype "bidirectional"))
      (node (ref "U$28") (pin "P$2") (pinfunction "P$1_P$2") (pintype "bidirectional"))
      (node (ref "U$28") (pin "P$3") (pinfunction "P$1_P$3") (pintype "bidirectional"))
      (node (ref "U$28") (pin "P$4") (pinfunction "P$1_P$4") (pintype "bidirectional"))
      (node (ref "U$28") (pin "P$5") (pinfunction "P$1_P$5") (pintype "bidirectional"))
      (node (ref "U$28") (pin "P$6") (pinfunction "P$1_P$6") (pintype "bidirectional"))
      (node (ref "U$28") (pin "P$7") (pinfunction "P$1_P$7") (pintype "bidirectional"))
    )
    (net (code "14") (name "Net-(U$29-P$1-PadP$2)") (class "Default")
      (node (ref "U$29") (pin "P$1") (pinfunction "P$1_P$1") (pintype "bidirectional"))
      (node (ref "U$29") (pin "P$2") (pinfunction "P$1_P$2") (pintype "bidirectional"))
      (node (ref "U$29") (pin "P$3") (pinfunction "P$1_P$3") (pintype "bidirectional"))
      (node (ref "U$29") (pin "P$4") (pinfunction "P$1_P$4") (pintype "bidirectional"))
      (node (ref "U$29") (pin "P$5") (pinfunction "P$1_P$5") (pintype "bidirectional"))
      (node (ref "U$29") (pin "P$6") (pinfunction "P$1_P$6") (pintype "bidirectional"))
      (node (ref "U$29") (pin "P$7") (pinfunction "P$1_P$7") (pintype "bidirectional"))
      (node (ref "U$30") (pin "P$1") (pinfunction "P$1_P$1") (pintype "bidirectional"))
      (node (ref "U$30") (pin "P$2") (pinfunction "P$1_P$2") (pintype "bidirectional"))
      (node (ref "U$30") (pin "P$3") (pinfunction "P$1_P$3") (pintype "bidirectional"))
      (node (ref "U$30") (pin "P$4") (pinfunction "P$1_P$4") (pintype "bidirectional"))
      (node (ref "U$30") (pin "P$5") (pinfunction "P$1_P$5") (pintype "bidirectional"))
      (node (ref "U$30") (pin "P$6") (pinfunction "P$1_P$6") (pintype "bidirectional"))
      (node (ref "U$30") (pin "P$7") (pinfunction "P$1_P$7") (pintype "bidirectional"))
      (node (ref "U$31") (pin "P$1") (pinfunction "P$1_P$1") (pintype "bidirectional"))
      (node (ref "U$31") (pin "P$2") (pinfunction "P$1_P$2") (pintype "bidirectional"))
      (node (ref "U$31") (pin "P$3") (pinfunction "P$1_P$3") (pintype "bidirectional"))
      (node (ref "U$31") (pin "P$4") (pinfunction "P$1_P$4") (pintype "bidirectional"))
      (node (ref "U$31") (pin "P$5") (pinfunction "P$1_P$5") (pintype "bidirectional"))
      (node (ref "U$31") (pin "P$6") (pinfunction "P$1_P$6") (pintype "bidirectional"))
      (node (ref "U$31") (pin "P$7") (pinfunction "P$1_P$7") (pintype "bidirectional"))
      (node (ref "U$32") (pin "P$1") (pinfunction "P$1_P$1") (pintype "bidirectional"))
      (node (ref "U$32") (pin "P$2") (pinfunction "P$1_P$2") (pintype "bidirectional"))
      (node (ref "U$32") (pin "P$3") (pinfunction "P$1_P$3") (pintype "bidirectional"))
      (node (ref "U$32") (pin "P$4") (pinfunction "P$1_P$4") (pintype "bidirectional"))
      (node (ref "U$32") (pin "P$5") (pinfunction "P$1_P$5") (pintype "bidirectional"))
      (node (ref "U$32") (pin "P$6") (pinfunction "P$1_P$6") (pintype "bidirectional"))
      (node (ref "U$32") (pin "P$7") (pinfunction "P$1_P$7") (pintype "bidirectional"))
      (node (ref "U$33") (pin "P$1") (pinfunction "P$1_P$1") (pintype "bidirectional"))
      (node (ref "U$33") (pin "P$2") (pinfunction "P$1_P$2") (pintype "bidirectional"))
      (node (ref "U$33") (pin "P$3") (pinfunction "P$1_P$3") (pintype "bidirectional"))
      (node (ref "U$33") (pin "P$4") (pinfunction "P$1_P$4") (pintype "bidirectional"))
      (node (ref "U$33") (pin "P$5") (pinfunction "P$1_P$5") (pintype "bidirectional"))
      (node (ref "U$33") (pin "P$6") (pinfunction "P$1_P$6") (pintype "bidirectional"))
      (node (ref "U$33") (pin "P$7") (pinfunction "P$1_P$7") (pintype "bidirectional"))
    )
    (net (code "15") (name "Net-(U$34-P$1-PadP$2)") (class "Default")
      (node (ref "U$34") (pin "P$1") (pinfunction "P$1_P$1") (pintype "bidirectional"))
      (node (ref "U$34") (pin "P$2") (pinfunction "P$1_P$2") (pintype "bidirectional"))
      (node (ref "U$34") (pin "P$3") (pinfunction "P$1_P$3") (pintype "bidirectional"))
      (node (ref "U$34") (pin "P$4") (pinfunction "P$1_P$4") (pintype "bidirectional"))
      (node (ref "U$34") (pin "P$5") (pinfunction "P$1_P$5") (pintype "bidirectional"))
      (node (ref "U$34") (pin "P$6") (pinfunction "P$1_P$6") (pintype "bidirectional"))
      (node (ref "U$34") (pin "P$7") (pinfunction "P$1_P$7") (pintype "bidirectional"))
    )
    (net (code "16") (name "Net-(U$35-P$1-PadP$2)") (class "Default")
      (node (ref "U$35") (pin "P$1") (pinfunction "P$1_P$1") (pintype "bidirectional"))
      (node (ref "U$35") (pin "P$2") (pinfunction "P$1_P$2") (pintype "bidirectional"))
      (node (ref "U$35") (pin "P$3") (pinfunction "P$1_P$3") (pintype "bidirectional"))
      (node (ref "U$35") (pin "P$4") (pinfunction "P$1_P$4") (pintype "bidirectional"))
      (node (ref "U$35") (pin "P$5") (pinfunction "P$1_P$5") (pintype "bidirectional"))
      (node (ref "U$35") (pin "P$6") (pinfunction "P$1_P$6") (pintype "bidirectional"))
      (node (ref "U$35") (pin "P$7") (pinfunction "P$1_P$7") (pintype "bidirectional"))
    )
    (net (code "17") (name "Net-(U$36-P$1-PadP$2)") (class "Default")
      (node (ref "U$36") (pin "P$1") (pinfunction "P$1_P$1") (pintype "bidirectional"))
      (node (ref "U$36") (pin "P$2") (pinfunction "P$1_P$2") (pintype "bidirectional"))
      (node (ref "U$36") (pin "P$3") (pinfunction "P$1_P$3") (pintype "bidirectional"))
      (node (ref "U$36") (pin "P$4") (pinfunction "P$1_P$4") (pintype "bidirectional"))
      (node (ref "U$36") (pin "P$5") (pinfunction "P$1_P$5") (pintype "bidirectional"))
      (node (ref "U$36") (pin "P$6") (pinfunction "P$1_P$6") (pintype "bidirectional"))
      (node (ref "U$36") (pin "P$7") (pinfunction "P$1_P$7") (pintype "bidirectional"))
    )
    (net (code "18") (name "Net-(U$37-P$1-PadP$2)") (class "Default")
      (node (ref "U$37") (pin "P$1") (pinfunction "P$1_P$1") (pintype "bidirectional"))
      (node (ref "U$37") (pin "P$2") (pinfunction "P$1_P$2") (pintype "bidirectional"))
      (node (ref "U$37") (pin "P$3") (pinfunction "P$1_P$3") (pintype "bidirectional"))
      (node (ref "U$37") (pin "P$4") (pinfunction "P$1_P$4") (pintype "bidirectional"))
      (node (ref "U$37") (pin "P$5") (pinfunction "P$1_P$5") (pintype "bidirectional"))
      (node (ref "U$37") (pin "P$6") (pinfunction "P$1_P$6") (pintype "bidirectional"))
      (node (ref "U$37") (pin "P$7") (pinfunction "P$1_P$7") (pintype "bidirectional"))
    )
    (net (code "19") (name "Net-(U$38-P$1-PadP$2)") (class "Default")
      (node (ref "U$38") (pin "P$1") (pinfunction "P$1_P$1") (pintype "bidirectional"))
      (node (ref "U$38") (pin "P$2") (pinfunction "P$1_P$2") (pintype "bidirectional"))
      (node (ref "U$38") (pin "P$3") (pinfunction "P$1_P$3") (pintype "bidirectional"))
      (node (ref "U$38") (pin "P$4") (pinfunction "P$1_P$4") (pintype "bidirectional"))
      (node (ref "U$38") (pin "P$5") (pinfunction "P$1_P$5") (pintype "bidirectional"))
      (node (ref "U$38") (pin "P$6") (pinfunction "P$1_P$6") (pintype "bidirectional"))
      (node (ref "U$38") (pin "P$7") (pinfunction "P$1_P$7") (pintype "bidirectional"))
    )
    (net (code "20") (name "Net-(U$39-P$1-PadP$2)") (class "Default")
      (node (ref "U$39") (pin "P$1") (pinfunction "P$1_P$1") (pintype "bidirectional"))
      (node (ref "U$39") (pin "P$2") (pinfunction "P$1_P$2") (pintype "bidirectional"))
      (node (ref "U$39") (pin "P$3") (pinfunction "P$1_P$3") (pintype "bidirectional"))
      (node (ref "U$39") (pin "P$4") (pinfunction "P$1_P$4") (pintype "bidirectional"))
      (node (ref "U$39") (pin "P$5") (pinfunction "P$1_P$5") (pintype "bidirectional"))
      (node (ref "U$39") (pin "P$6") (pinfunction "P$1_P$6") (pintype "bidirectional"))
      (node (ref "U$39") (pin "P$7") (pinfunction "P$1_P$7") (pintype "bidirectional"))
    )
    (net (code "21") (name "Net-(U$40-P$1-PadP$2)") (class "Default")
      (node (ref "U$40") (pin "P$1") (pinfunction "P$1_P$1") (pintype "bidirectional"))
      (node (ref "U$40") (pin "P$2") (pinfunction "P$1_P$2") (pintype "bidirectional"))
      (node (ref "U$40") (pin "P$3") (pinfunction "P$1_P$3") (pintype "bidirectional"))
      (node (ref "U$40") (pin "P$4") (pinfunction "P$1_P$4") (pintype "bidirectional"))
      (node (ref "U$40") (pin "P$5") (pinfunction "P$1_P$5") (pintype "bidirectional"))
      (node (ref "U$40") (pin "P$6") (pinfunction "P$1_P$6") (pintype "bidirectional"))
      (node (ref "U$40") (pin "P$7") (pinfunction "P$1_P$7") (pintype "bidirectional"))
    )
    (net (code "22") (name "Net-(U$41-P$1-PadP$2)") (class "Default")
      (node (ref "U$41") (pin "P$1") (pinfunction "P$1_P$1") (pintype "bidirectional"))
      (node (ref "U$41") (pin "P$2") (pinfunction "P$1_P$2") (pintype "bidirectional"))
      (node (ref "U$41") (pin "P$3") (pinfunction "P$1_P$3") (pintype "bidirectional"))
      (node (ref "U$41") (pin "P$4") (pinfunction "P$1_P$4") (pintype "bidirectional"))
      (node (ref "U$41") (pin "P$5") (pinfunction "P$1_P$5") (pintype "bidirectional"))
      (node (ref "U$41") (pin "P$6") (pinfunction "P$1_P$6") (pintype "bidirectional"))
      (node (ref "U$41") (pin "P$7") (pinfunction "P$1_P$7") (pintype "bidirectional"))
    )
    (net (code "23") (name "Net-(U$42-P$1-PadP$2)") (class "Default")
      (node (ref "U$42") (pin "P$1") (pinfunction "P$1_P$1") (pintype "bidirectional"))
      (node (ref "U$42") (pin "P$2") (pinfunction "P$1_P$2") (pintype "bidirectional"))
      (node (ref "U$42") (pin "P$3") (pinfunction "P$1_P$3") (pintype "bidirectional"))
      (node (ref "U$42") (pin "P$4") (pinfunction "P$1_P$4") (pintype "bidirectional"))
      (node (ref "U$42") (pin "P$5") (pinfunction "P$1_P$5") (pintype "bidirectional"))
      (node (ref "U$42") (pin "P$6") (pinfunction "P$1_P$6") (pintype "bidirectional"))
      (node (ref "U$42") (pin "P$7") (pinfunction "P$1_P$7") (pintype "bidirectional"))
    )
    (net (code "24") (name "Net-(U$43-P$1-PadP$2)") (class "Default")
      (node (ref "U$43") (pin "P$1") (pinfunction "P$1_P$1") (pintype "bidirectional"))
      (node (ref "U$43") (pin "P$2") (pinfunction "P$1_P$2") (pintype "bidirectional"))
      (node (ref "U$43") (pin "P$3") (pinfunction "P$1_P$3") (pintype "bidirectional"))
      (node (ref "U$43") (pin "P$4") (pinfunction "P$1_P$4") (pintype "bidirectional"))
      (node (ref "U$43") (pin "P$5") (pinfunction "P$1_P$5") (pintype "bidirectional"))
      (node (ref "U$43") (pin "P$6") (pinfunction "P$1_P$6") (pintype "bidirectional"))
      (node (ref "U$43") (pin "P$7") (pinfunction "P$1_P$7") (pintype "bidirectional"))
    )
    (net (code "25") (name "Net-(U$44-P$1-PadP$2)") (class "Default")
      (node (ref "U$44") (pin "P$1") (pinfunction "P$1_P$1") (pintype "bidirectional"))
      (node (ref "U$44") (pin "P$2") (pinfunction "P$1_P$2") (pintype "bidirectional"))
      (node (ref "U$44") (pin "P$3") (pinfunction "P$1_P$3") (pintype "bidirectional"))
      (node (ref "U$44") (pin "P$4") (pinfunction "P$1_P$4") (pintype "bidirectional"))
      (node (ref "U$44") (pin "P$5") (pinfunction "P$1_P$5") (pintype "bidirectional"))
      (node (ref "U$44") (pin "P$6") (pinfunction "P$1_P$6") (pintype "bidirectional"))
      (node (ref "U$44") (pin "P$7") (pinfunction "P$1_P$7") (pintype "bidirectional"))
    )
    (net (code "26") (name "Net-(U$45-P$1-PadP$2)") (class "Default")
      (node (ref "U$45") (pin "P$1") (pinfunction "P$1_P$1") (pintype "bidirectional"))
      (node (ref "U$45") (pin "P$2") (pinfunction "P$1_P$2") (pintype "bidirectional"))
      (node (ref "U$45") (pin "P$3") (pinfunction "P$1_P$3") (pintype "bidirectional"))
      (node (ref "U$45") (pin "P$4") (pinfunction "P$1_P$4") (pintype "bidirectional"))
      (node (ref "U$45") (pin "P$5") (pinfunction "P$1_P$5") (pintype "bidirectional"))
      (node (ref "U$45") (pin "P$6") (pinfunction "P$1_P$6") (pintype "bidirectional"))
      (node (ref "U$45") (pin "P$7") (pinfunction "P$1_P$7") (pintype "bidirectional"))
    )
    (net (code "27") (name "Net-(U$46-P$1-PadP$2)") (class "Default")
      (node (ref "U$46") (pin "P$1") (pinfunction "P$1_P$1") (pintype "bidirectional"))
      (node (ref "U$46") (pin "P$2") (pinfunction "P$1_P$2") (pintype "bidirectional"))
      (node (ref "U$46") (pin "P$3") (pinfunction "P$1_P$3") (pintype "bidirectional"))
      (node (ref "U$46") (pin "P$4") (pinfunction "P$1_P$4") (pintype "bidirectional"))
      (node (ref "U$46") (pin "P$5") (pinfunction "P$1_P$5") (pintype "bidirectional"))
      (node (ref "U$46") (pin "P$6") (pinfunction "P$1_P$6") (pintype "bidirectional"))
      (node (ref "U$46") (pin "P$7") (pinfunction "P$1_P$7") (pintype "bidirectional"))
    )
    (net (code "28") (name "Net-(U$47-P$1-PadP$2)") (class "Default")
      (node (ref "U$47") (pin "P$1") (pinfunction "P$1_P$1") (pintype "bidirectional"))
      (node (ref "U$47") (pin "P$2") (pinfunction "P$1_P$2") (pintype "bidirectional"))
      (node (ref "U$47") (pin "P$3") (pinfunction "P$1_P$3") (pintype "bidirectional"))
      (node (ref "U$47") (pin "P$4") (pinfunction "P$1_P$4") (pintype "bidirectional"))
      (node (ref "U$47") (pin "P$5") (pinfunction "P$1_P$5") (pintype "bidirectional"))
      (node (ref "U$47") (pin "P$6") (pinfunction "P$1_P$6") (pintype "bidirectional"))
      (node (ref "U$47") (pin "P$7") (pinfunction "P$1_P$7") (pintype "bidirectional"))
    )
    (net (code "29") (name "Net-(U$48-P$1-PadP$2)") (class "Default")
      (node (ref "U$48") (pin "P$1") (pinfunction "P$1_P$1") (pintype "bidirectional"))
      (node (ref "U$48") (pin "P$2") (pinfunction "P$1_P$2") (pintype "bidirectional"))
      (node (ref "U$48") (pin "P$3") (pinfunction "P$1_P$3") (pintype "bidirectional"))
      (node (ref "U$48") (pin "P$4") (pinfunction "P$1_P$4") (pintype "bidirectional"))
      (node (ref "U$48") (pin "P$5") (pinfunction "P$1_P$5") (pintype "bidirectional"))
      (node (ref "U$48") (pin "P$6") (pinfunction "P$1_P$6") (pintype "bidirectional"))
      (node (ref "U$48") (pin "P$7") (pinfunction "P$1_P$7") (pintype "bidirectional"))
    )
    (net (code "30") (name "Net-(U$49-P$1-PadP$2)") (class "Default")
      (node (ref "U$49") (pin "P$1") (pinfunction "P$1_P$1") (pintype "bidirectional"))
      (node (ref "U$49") (pin "P$2") (pinfunction "P$1_P$2") (pintype "bidirectional"))
      (node (ref "U$49") (pin "P$3") (pinfunction "P$1_P$3") (pintype "bidirectional"))
      (node (ref "U$49") (pin "P$4") (pinfunction "P$1_P$4") (pintype "bidirectional"))
      (node (ref "U$49") (pin "P$5") (pinfunction "P$1_P$5") (pintype "bidirectional"))
      (node (ref "U$49") (pin "P$6") (pinfunction "P$1_P$6") (pintype "bidirectional"))
      (node (ref "U$49") (pin "P$7") (pinfunction "P$1_P$7") (pintype "bidirectional"))
    )
    (net (code "31") (name "Net-(U$50-P$1-PadP$2)") (class "Default")
      (node (ref "U$50") (pin "P$1") (pinfunction "P$1_P$1") (pintype "bidirectional"))
      (node (ref "U$50") (pin "P$2") (pinfunction "P$1_P$2") (pintype "bidirectional"))
      (node (ref "U$50") (pin "P$3") (pinfunction "P$1_P$3") (pintype "bidirectional"))
      (node (ref "U$50") (pin "P$4") (pinfunction "P$1_P$4") (pintype "bidirectional"))
      (node (ref "U$50") (pin "P$5") (pinfunction "P$1_P$5") (pintype "bidirectional"))
      (node (ref "U$50") (pin "P$6") (pinfunction "P$1_P$6") (pintype "bidirectional"))
      (node (ref "U$50") (pin "P$7") (pinfunction "P$1_P$7") (pintype "bidirectional"))
    )
    (net (code "32") (name "Net-(U$51-P$1-PadP$2)") (class "Default")
      (node (ref "U$51") (pin "P$1") (pinfunction "P$1_P$1") (pintype "bidirectional"))
      (node (ref "U$51") (pin "P$2") (pinfunction "P$1_P$2") (pintype "bidirectional"))
      (node (ref "U$51") (pin "P$3") (pinfunction "P$1_P$3") (pintype "bidirectional"))
      (node (ref "U$51") (pin "P$4") (pinfunction "P$1_P$4") (pintype "bidirectional"))
      (node (ref "U$51") (pin "P$5") (pinfunction "P$1_P$5") (pintype "bidirectional"))
      (node (ref "U$51") (pin "P$6") (pinfunction "P$1_P$6") (pintype "bidirectional"))
      (node (ref "U$51") (pin "P$7") (pinfunction "P$1_P$7") (pintype "bidirectional"))
    )
    (net (code "33") (name "Net-(U$52-P$1-PadP$2)") (class "Default")
      (node (ref "U$52") (pin "P$1") (pinfunction "P$1_P$1") (pintype "bidirectional"))
      (node (ref "U$52") (pin "P$2") (pinfunction "P$1_P$2") (pintype "bidirectional"))
      (node (ref "U$52") (pin "P$3") (pinfunction "P$1_P$3") (pintype "bidirectional"))
      (node (ref "U$52") (pin "P$4") (pinfunction "P$1_P$4") (pintype "bidirectional"))
      (node (ref "U$52") (pin "P$5") (pinfunction "P$1_P$5") (pintype "bidirectional"))
      (node (ref "U$52") (pin "P$6") (pinfunction "P$1_P$6") (pintype "bidirectional"))
      (node (ref "U$52") (pin "P$7") (pinfunction "P$1_P$7") (pintype "bidirectional"))
    )
    (net (code "34") (name "Net-(U$53-P$1-PadP$2)") (class "Default")
      (node (ref "U$53") (pin "P$1") (pinfunction "P$1_P$1") (pintype "bidirectional"))
      (node (ref "U$53") (pin "P$2") (pinfunction "P$1_P$2") (pintype "bidirectional"))
      (node (ref "U$53") (pin "P$3") (pinfunction "P$1_P$3") (pintype "bidirectional"))
      (node (ref "U$53") (pin "P$4") (pinfunction "P$1_P$4") (pintype "bidirectional"))
      (node (ref "U$53") (pin "P$5") (pinfunction "P$1_P$5") (pintype "bidirectional"))
      (node (ref "U$53") (pin "P$6") (pinfunction "P$1_P$6") (pintype "bidirectional"))
      (node (ref "U$53") (pin "P$7") (pinfunction "P$1_P$7") (pintype "bidirectional"))
    )
    (net (code "35") (name "Net-(U$54-P$1-PadP$2)") (class "Default")
      (node (ref "U$54") (pin "P$1") (pinfunction "P$1_P$1") (pintype "bidirectional"))
      (node (ref "U$54") (pin "P$2") (pinfunction "P$1_P$2") (pintype "bidirectional"))
      (node (ref "U$54") (pin "P$3") (pinfunction "P$1_P$3") (pintype "bidirectional"))
      (node (ref "U$54") (pin "P$4") (pinfunction "P$1_P$4") (pintype "bidirectional"))
      (node (ref "U$54") (pin "P$5") (pinfunction "P$1_P$5") (pintype "bidirectional"))
      (node (ref "U$54") (pin "P$6") (pinfunction "P$1_P$6") (pintype "bidirectional"))
      (node (ref "U$54") (pin "P$7") (pinfunction "P$1_P$7") (pintype "bidirectional"))
    )
    (net (code "36") (name "Net-(U$55-P$1-PadP$2)") (class "Default")
      (node (ref "U$55") (pin "P$1") (pinfunction "P$1_P$1") (pintype "bidirectional"))
      (node (ref "U$55") (pin "P$2") (pinfunction "P$1_P$2") (pintype "bidirectional"))
      (node (ref "U$55") (pin "P$3") (pinfunction "P$1_P$3") (pintype "bidirectional"))
      (node (ref "U$55") (pin "P$4") (pinfunction "P$1_P$4") (pintype "bidirectional"))
      (node (ref "U$55") (pin "P$5") (pinfunction "P$1_P$5") (pintype "bidirectional"))
      (node (ref "U$55") (pin "P$6") (pinfunction "P$1_P$6") (pintype "bidirectional"))
      (node (ref "U$55") (pin "P$7") (pinfunction "P$1_P$7") (pintype "bidirectional"))
    )
    (net (code "37") (name "Net-(U$56-P$1-PadP$2)") (class "Default")
      (node (ref "U$56") (pin "P$1") (pinfunction "P$1_P$1") (pintype "bidirectional"))
      (node (ref "U$56") (pin "P$2") (pinfunction "P$1_P$2") (pintype "bidirectional"))
      (node (ref "U$56") (pin "P$3") (pinfunction "P$1_P$3") (pintype "bidirectional"))
      (node (ref "U$56") (pin "P$4") (pinfunction "P$1_P$4") (pintype "bidirectional"))
      (node (ref "U$56") (pin "P$5") (pinfunction "P$1_P$5") (pintype "bidirectional"))
      (node (ref "U$56") (pin "P$6") (pinfunction "P$1_P$6") (pintype "bidirectional"))
      (node (ref "U$56") (pin "P$7") (pinfunction "P$1_P$7") (pintype "bidirectional"))
    )
    (net (code "38") (name "Net-(U$57-P$1-PadP$2)") (class "Default")
      (node (ref "U$57") (pin "P$1") (pinfunction "P$1_P$1") (pintype "bidirectional"))
      (node (ref "U$57") (pin "P$2") (pinfunction "P$1_P$2") (pintype "bidirectional"))
      (node (ref "U$57") (pin "P$3") (pinfunction "P$1_P$3") (pintype "bidirectional"))
      (node (ref "U$57") (pin "P$4") (pinfunction "P$1_P$4") (pintype "bidirectional"))
      (node (ref "U$57") (pin "P$5") (pinfunction "P$1_P$5") (pintype "bidirectional"))
      (node (ref "U$57") (pin "P$6") (pinfunction "P$1_P$6") (pintype "bidirectional"))
      (node (ref "U$57") (pin "P$7") (pinfunction "P$1_P$7") (pintype "bidirectional"))
    )
    (net (code "39") (name "Net-(U$58-P$1-PadP$2)") (class "Default")
      (node (ref "U$58") (pin "P$1") (pinfunction "P$1_P$1") (pintype "bidirectional"))
      (node (ref "U$58") (pin "P$2") (pinfunction "P$1_P$2") (pintype "bidirectional"))
      (node (ref "U$58") (pin "P$3") (pinfunction "P$1_P$3") (pintype "bidirectional"))
      (node (ref "U$58") (pin "P$4") (pinfunction "P$1_P$4") (pintype "bidirectional"))
      (node (ref "U$58") (pin "P$5") (pinfunction "P$1_P$5") (pintype "bidirectional"))
      (node (ref "U$58") (pin "P$6") (pinfunction "P$1_P$6") (pintype "bidirectional"))
      (node (ref "U$58") (pin "P$7") (pinfunction "P$1_P$7") (pintype "bidirectional"))
    )
    (net (code "40") (name "Net-(U$59-P$1-PadP$2)") (class "Default")
      (node (ref "U$59") (pin "P$1") (pinfunction "P$1_P$1") (pintype "bidirectional"))
      (node (ref "U$59") (pin "P$2") (pinfunction "P$1_P$2") (pintype "bidirectional"))
      (node (ref "U$59") (pin "P$3") (pinfunction "P$1_P$3") (pintype "bidirectional"))
      (node (ref "U$59") (pin "P$4") (pinfunction "P$1_P$4") (pintype "bidirectional"))
      (node (ref "U$59") (pin "P$5") (pinfunction "P$1_P$5") (pintype "bidirectional"))
      (node (ref "U$59") (pin "P$6") (pinfunction "P$1_P$6") (pintype "bidirectional"))
      (node (ref "U$59") (pin "P$7") (pinfunction "P$1_P$7") (pintype "bidirectional"))
    )
    (net (code "41") (name "Net-(U$60-P$1-PadP$2)") (class "Default")
      (node (ref "U$60") (pin "P$1") (pinfunction "P$1_P$1") (pintype "bidirectional"))
      (node (ref "U$60") (pin "P$2") (pinfunction "P$1_P$2") (pintype "bidirectional"))
      (node (ref "U$60") (pin "P$3") (pinfunction "P$1_P$3") (pintype "bidirectional"))
      (node (ref "U$60") (pin "P$4") (pinfunction "P$1_P$4") (pintype "bidirectional"))
      (node (ref "U$60") (pin "P$5") (pinfunction "P$1_P$5") (pintype "bidirectional"))
      (node (ref "U$60") (pin "P$6") (pinfunction "P$1_P$6") (pintype "bidirectional"))
      (node (ref "U$60") (pin "P$7") (pinfunction "P$1_P$7") (pintype "bidirectional"))
    )
    (net (code "42") (name "Net-(U$61-P$1-PadP$2)") (class "Default")
      (node (ref "U$61") (pin "P$1") (pinfunction "P$1_P$1") (pintype "bidirectional"))
      (node (ref "U$61") (pin "P$2") (pinfunction "P$1_P$2") (pintype "bidirectional"))
      (node (ref "U$61") (pin "P$3") (pinfunction "P$1_P$3") (pintype "bidirectional"))
      (node (ref "U$61") (pin "P$4") (pinfunction "P$1_P$4") (pintype "bidirectional"))
      (node (ref "U$61") (pin "P$5") (pinfunction "P$1_P$5") (pintype "bidirectional"))
      (node (ref "U$61") (pin "P$6") (pinfunction "P$1_P$6") (pintype "bidirectional"))
      (node (ref "U$61") (pin "P$7") (pinfunction "P$1_P$7") (pintype "bidirectional"))
    )
    (net (code "43") (name "Net-(U$62-P$1-PadP$2)") (class "Default")
      (node (ref "U$62") (pin "P$1") (pinfunction "P$1_P$1") (pintype "bidirectional"))
      (node (ref "U$62") (pin "P$2") (pinfunction "P$1_P$2") (pintype "bidirectional"))
      (node (ref "U$62") (pin "P$3") (pinfunction "P$1_P$3") (pintype "bidirectional"))
      (node (ref "U$62") (pin "P$4") (pinfunction "P$1_P$4") (pintype "bidirectional"))
      (node (ref "U$62") (pin "P$5") (pinfunction "P$1_P$5") (pintype "bidirectional"))
      (node (ref "U$62") (pin "P$6") (pinfunction "P$1_P$6") (pintype "bidirectional"))
      (node (ref "U$62") (pin "P$7") (pinfunction "P$1_P$7") (pintype "bidirectional"))
    )
    (net (code "44") (name "Net-(U$63-P$1-PadP$2)") (class "Default")
      (node (ref "U$63") (pin "P$1") (pinfunction "P$1_P$1") (pintype "bidirectional"))
      (node (ref "U$63") (pin "P$2") (pinfunction "P$1_P$2") (pintype "bidirectional"))
      (node (ref "U$63") (pin "P$3") (pinfunction "P$1_P$3") (pintype "bidirectional"))
      (node (ref "U$63") (pin "P$4") (pinfunction "P$1_P$4") (pintype "bidirectional"))
      (node (ref "U$63") (pin "P$5") (pinfunction "P$1_P$5") (pintype "bidirectional"))
      (node (ref "U$63") (pin "P$6") (pinfunction "P$1_P$6") (pintype "bidirectional"))
      (node (ref "U$63") (pin "P$7") (pinfunction "P$1_P$7") (pintype "bidirectional"))
    )
    (net (code "45") (name "Net-(U$64-P$1-PadP$2)") (class "Default")
      (node (ref "U$64") (pin "P$1") (pinfunction "P$1_P$1") (pintype "bidirectional"))
      (node (ref "U$64") (pin "P$2") (pinfunction "P$1_P$2") (pintype "bidirectional"))
      (node (ref "U$64") (pin "P$3") (pinfunction "P$1_P$3") (pintype "bidirectional"))
      (node (ref "U$64") (pin "P$4") (pinfunction "P$1_P$4") (pintype "bidirectional"))
      (node (ref "U$64") (pin "P$5") (pinfunction "P$1_P$5") (pintype "bidirectional"))
      (node (ref "U$64") (pin "P$6") (pinfunction "P$1_P$6") (pintype "bidirectional"))
      (node (ref "U$64") (pin "P$7") (pinfunction "P$1_P$7") (pintype "bidirectional"))
    )
    (net (code "46") (name "Net-(U$65-P$1-PadP$2)") (class "Default")
      (node (ref "U$65") (pin "P$1") (pinfunction "P$1_P$1") (pintype "bidirectional"))
      (node (ref "U$65") (pin "P$2") (pinfunction "P$1_P$2") (pintype "bidirectional"))
      (node (ref "U$65") (pin "P$3") (pinfunction "P$1_P$3") (pintype "bidirectional"))
      (node (ref "U$65") (pin "P$4") (pinfunction "P$1_P$4") (pintype "bidirectional"))
      (node (ref "U$65") (pin "P$5") (pinfunction "P$1_P$5") (pintype "bidirectional"))
      (node (ref "U$65") (pin "P$6") (pinfunction "P$1_P$6") (pintype "bidirectional"))
      (node (ref "U$65") (pin "P$7") (pinfunction "P$1_P$7") (pintype "bidirectional"))
    )
    (net (code "47") (name "Net-(U$66-P$1-PadP$2)") (class "Default")
      (node (ref "U$66") (pin "P$1") (pinfunction "P$1_P$1") (pintype "bidirectional"))
      (node (ref "U$66") (pin "P$2") (pinfunction "P$1_P$2") (pintype "bidirectional"))
      (node (ref "U$66") (pin "P$3") (pinfunction "P$1_P$3") (pintype "bidirectional"))
      (node (ref "U$66") (pin "P$4") (pinfunction "P$1_P$4") (pintype "bidirectional"))
      (node (ref "U$66") (pin "P$5") (pinfunction "P$1_P$5") (pintype "bidirectional"))
      (node (ref "U$66") (pin "P$6") (pinfunction "P$1_P$6") (pintype "bidirectional"))
      (node (ref "U$66") (pin "P$7") (pinfunction "P$1_P$7") (pintype "bidirectional"))
    )
    (net (code "48") (name "Net-(U$67-P$1-PadP$2)") (class "Default")
      (node (ref "U$67") (pin "P$1") (pinfunction "P$1_P$1") (pintype "bidirectional"))
      (node (ref "U$67") (pin "P$2") (pinfunction "P$1_P$2") (pintype "bidirectional"))
      (node (ref "U$67") (pin "P$3") (pinfunction "P$1_P$3") (pintype "bidirectional"))
      (node (ref "U$67") (pin "P$4") (pinfunction "P$1_P$4") (pintype "bidirectional"))
      (node (ref "U$67") (pin "P$5") (pinfunction "P$1_P$5") (pintype "bidirectional"))
      (node (ref "U$67") (pin "P$6") (pinfunction "P$1_P$6") (pintype "bidirectional"))
      (node (ref "U$67") (pin "P$7") (pinfunction "P$1_P$7") (pintype "bidirectional"))
    )
    (net (code "49") (name "Net-(U$68-P$1-PadP$2)") (class "Default")
      (node (ref "U$68") (pin "P$1") (pinfunction "P$1_P$1") (pintype "bidirectional"))
      (node (ref "U$68") (pin "P$2") (pinfunction "P$1_P$2") (pintype "bidirectional"))
      (node (ref "U$68") (pin "P$3") (pinfunction "P$1_P$3") (pintype "bidirectional"))
      (node (ref "U$68") (pin "P$4") (pinfunction "P$1_P$4") (pintype "bidirectional"))
      (node (ref "U$68") (pin "P$5") (pinfunction "P$1_P$5") (pintype "bidirectional"))
      (node (ref "U$68") (pin "P$6") (pinfunction "P$1_P$6") (pintype "bidirectional"))
      (node (ref "U$68") (pin "P$7") (pinfunction "P$1_P$7") (pintype "bidirectional"))
    )
    (net (code "50") (name "Net-(U$69-P$1-PadP$2)") (class "Default")
      (node (ref "U$69") (pin "P$1") (pinfunction "P$1_P$1") (pintype "bidirectional"))
      (node (ref "U$69") (pin "P$2") (pinfunction "P$1_P$2") (pintype "bidirectional"))
      (node (ref "U$69") (pin "P$3") (pinfunction "P$1_P$3") (pintype "bidirectional"))
      (node (ref "U$69") (pin "P$4") (pinfunction "P$1_P$4") (pintype "bidirectional"))
      (node (ref "U$69") (pin "P$5") (pinfunction "P$1_P$5") (pintype "bidirectional"))
      (node (ref "U$69") (pin "P$6") (pinfunction "P$1_P$6") (pintype "bidirectional"))
      (node (ref "U$69") (pin "P$7") (pinfunction "P$1_P$7") (pintype "bidirectional"))
    )
    (net (code "51") (name "Net-(U$70-P$1-PadP$2)") (class "Default")
      (node (ref "U$70") (pin "P$1") (pinfunction "P$1_P$1") (pintype "bidirectional"))
      (node (ref "U$70") (pin "P$2") (pinfunction "P$1_P$2") (pintype "bidirectional"))
      (node (ref "U$70") (pin "P$3") (pinfunction "P$1_P$3") (pintype "bidirectional"))
      (node (ref "U$70") (pin "P$4") (pinfunction "P$1_P$4") (pintype "bidirectional"))
      (node (ref "U$70") (pin "P$5") (pinfunction "P$1_P$5") (pintype "bidirectional"))
      (node (ref "U$70") (pin "P$6") (pinfunction "P$1_P$6") (pintype "bidirectional"))
      (node (ref "U$70") (pin "P$7") (pinfunction "P$1_P$7") (pintype "bidirectional"))
    )
    (net (code "52") (name "Net-(U$71-P$1-PadP$2)") (class "Default")
      (node (ref "U$71") (pin "P$1") (pinfunction "P$1_P$1") (pintype "bidirectional"))
      (node (ref "U$71") (pin "P$2") (pinfunction "P$1_P$2") (pintype "bidirectional"))
      (node (ref "U$71") (pin "P$3") (pinfunction "P$1_P$3") (pintype "bidirectional"))
      (node (ref "U$71") (pin "P$4") (pinfunction "P$1_P$4") (pintype "bidirectional"))
      (node (ref "U$71") (pin "P$5") (pinfunction "P$1_P$5") (pintype "bidirectional"))
      (node (ref "U$71") (pin "P$6") (pinfunction "P$1_P$6") (pintype "bidirectional"))
      (node (ref "U$71") (pin "P$7") (pinfunction "P$1_P$7") (pintype "bidirectional"))
    )
    (net (code "53") (name "Net-(U$72-P$1-PadP$2)") (class "Default")
      (node (ref "U$72") (pin "P$1") (pinfunction "P$1_P$1") (pintype "bidirectional"))
      (node (ref "U$72") (pin "P$2") (pinfunction "P$1_P$2") (pintype "bidirectional"))
      (node (ref "U$72") (pin "P$3") (pinfunction "P$1_P$3") (pintype "bidirectional"))
      (node (ref "U$72") (pin "P$4") (pinfunction "P$1_P$4") (pintype "bidirectional"))
      (node (ref "U$72") (pin "P$5") (pinfunction "P$1_P$5") (pintype "bidirectional"))
      (node (ref "U$72") (pin "P$6") (pinfunction "P$1_P$6") (pintype "bidirectional"))
      (node (ref "U$72") (pin "P$7") (pinfunction "P$1_P$7") (pintype "bidirectional"))
    )
    (net (code "54") (name "Net-(U$73-P$1-PadP$2)") (class "Default")
      (node (ref "U$73") (pin "P$1") (pinfunction "P$1_P$1") (pintype "bidirectional"))
      (node (ref "U$73") (pin "P$2") (pinfunction "P$1_P$2") (pintype "bidirectional"))
      (node (ref "U$73") (pin "P$3") (pinfunction "P$1_P$3") (pintype "bidirectional"))
      (node (ref "U$73") (pin "P$4") (pinfunction "P$1_P$4") (pintype "bidirectional"))
      (node (ref "U$73") (pin "P$5") (pinfunction "P$1_P$5") (pintype "bidirectional"))
      (node (ref "U$73") (pin "P$6") (pinfunction "P$1_P$6") (pintype "bidirectional"))
      (node (ref "U$73") (pin "P$7") (pinfunction "P$1_P$7") (pintype "bidirectional"))
    )
    (net (code "55") (name "Net-(U$74-P$1-PadP$2)") (class "Default")
      (node (ref "U$74") (pin "P$1") (pinfunction "P$1_P$1") (pintype "bidirectional"))
      (node (ref "U$74") (pin "P$2") (pinfunction "P$1_P$2") (pintype "bidirectional"))
      (node (ref "U$74") (pin "P$3") (pinfunction "P$1_P$3") (pintype "bidirectional"))
      (node (ref "U$74") (pin "P$4") (pinfunction "P$1_P$4") (pintype "bidirectional"))
      (node (ref "U$74") (pin "P$5") (pinfunction "P$1_P$5") (pintype "bidirectional"))
      (node (ref "U$74") (pin "P$6") (pinfunction "P$1_P$6") (pintype "bidirectional"))
      (node (ref "U$74") (pin "P$7") (pinfunction "P$1_P$7") (pintype "bidirectional"))
    )
    (net (code "56") (name "Net-(U$75-P$1-PadP$2)") (class "Default")
      (node (ref "U$75") (pin "P$1") (pinfunction "P$1_P$1") (pintype "bidirectional"))
      (node (ref "U$75") (pin "P$2") (pinfunction "P$1_P$2") (pintype "bidirectional"))
      (node (ref "U$75") (pin "P$3") (pinfunction "P$1_P$3") (pintype "bidirectional"))
      (node (ref "U$75") (pin "P$4") (pinfunction "P$1_P$4") (pintype "bidirectional"))
      (node (ref "U$75") (pin "P$5") (pinfunction "P$1_P$5") (pintype "bidirectional"))
      (node (ref "U$75") (pin "P$6") (pinfunction "P$1_P$6") (pintype "bidirectional"))
      (node (ref "U$75") (pin "P$7") (pinfunction "P$1_P$7") (pintype "bidirectional"))
    )
    (net (code "57") (name "Net-(U$76-P$1-PadP$2)") (class "Default")
      (node (ref "U$76") (pin "P$1") (pinfunction "P$1_P$1") (pintype "bidirectional"))
      (node (ref "U$76") (pin "P$2") (pinfunction "P$1_P$2") (pintype "bidirectional"))
      (node (ref "U$76") (pin "P$3") (pinfunction "P$1_P$3") (pintype "bidirectional"))
      (node (ref "U$76") (pin "P$4") (pinfunction "P$1_P$4") (pintype "bidirectional"))
      (node (ref "U$76") (pin "P$5") (pinfunction "P$1_P$5") (pintype "bidirectional"))
      (node (ref "U$76") (pin "P$6") (pinfunction "P$1_P$6") (pintype "bidirectional"))
      (node (ref "U$76") (pin "P$7") (pinfunction "P$1_P$7") (pintype "bidirectional"))
    )
    (net (code "58") (name "Net-(U$77-P$1-PadP$2)") (class "Default")
      (node (ref "U$77") (pin "P$1") (pinfunction "P$1_P$1") (pintype "bidirectional"))
      (node (ref "U$77") (pin "P$2") (pinfunction "P$1_P$2") (pintype "bidirectional"))
      (node (ref "U$77") (pin "P$3") (pinfunction "P$1_P$3") (pintype "bidirectional"))
      (node (ref "U$77") (pin "P$4") (pinfunction "P$1_P$4") (pintype "bidirectional"))
      (node (ref "U$77") (pin "P$5") (pinfunction "P$1_P$5") (pintype "bidirectional"))
      (node (ref "U$77") (pin "P$6") (pinfunction "P$1_P$6") (pintype "bidirectional"))
      (node (ref "U$77") (pin "P$7") (pinfunction "P$1_P$7") (pintype "bidirectional"))
    )
    (net (code "59") (name "Net-(U$78-P$1-PadP$2)") (class "Default")
      (node (ref "U$78") (pin "P$1") (pinfunction "P$1_P$1") (pintype "bidirectional"))
      (node (ref "U$78") (pin "P$2") (pinfunction "P$1_P$2") (pintype "bidirectional"))
      (node (ref "U$78") (pin "P$3") (pinfunction "P$1_P$3") (pintype "bidirectional"))
      (node (ref "U$78") (pin "P$4") (pinfunction "P$1_P$4") (pintype "bidirectional"))
      (node (ref "U$78") (pin "P$5") (pinfunction "P$1_P$5") (pintype "bidirectional"))
      (node (ref "U$78") (pin "P$6") (pinfunction "P$1_P$6") (pintype "bidirectional"))
      (node (ref "U$78") (pin "P$7") (pinfunction "P$1_P$7") (pintype "bidirectional"))
    )
    (net (code "60") (name "Net-(U$79-P$1-PadP$2)") (class "Default")
      (node (ref "U$79") (pin "P$1") (pinfunction "P$1_P$1") (pintype "bidirectional"))
      (node (ref "U$79") (pin "P$2") (pinfunction "P$1_P$2") (pintype "bidirectional"))
      (node (ref "U$79") (pin "P$3") (pinfunction "P$1_P$3") (pintype "bidirectional"))
      (node (ref "U$79") (pin "P$4") (pinfunction "P$1_P$4") (pintype "bidirectional"))
      (node (ref "U$79") (pin "P$5") (pinfunction "P$1_P$5") (pintype "bidirectional"))
      (node (ref "U$79") (pin "P$6") (pinfunction "P$1_P$6") (pintype "bidirectional"))
      (node (ref "U$79") (pin "P$7") (pinfunction "P$1_P$7") (pintype "bidirectional"))
    )
    (net (code "61") (name "Net-(U$80-P$1-PadP$2)") (class "Default")
      (node (ref "U$80") (pin "P$1") (pinfunction "P$1_P$1") (pintype "bidirectional"))
      (node (ref "U$80") (pin "P$2") (pinfunction "P$1_P$2") (pintype "bidirectional"))
      (node (ref "U$80") (pin "P$3") (pinfunction "P$1_P$3") (pintype "bidirectional"))
      (node (ref "U$80") (pin "P$4") (pinfunction "P$1_P$4") (pintype "bidirectional"))
      (node (ref "U$80") (pin "P$5") (pinfunction "P$1_P$5") (pintype "bidirectional"))
      (node (ref "U$80") (pin "P$6") (pinfunction "P$1_P$6") (pintype "bidirectional"))
      (node (ref "U$80") (pin "P$7") (pinfunction "P$1_P$7") (pintype "bidirectional"))
    )
    (net (code "62") (name "Net-(U$81-P$1-PadP$2)") (class "Default")
      (node (ref "U$81") (pin "P$1") (pinfunction "P$1_P$1") (pintype "bidirectional"))
      (node (ref "U$81") (pin "P$2") (pinfunction "P$1_P$2") (pintype "bidirectional"))
      (node (ref "U$81") (pin "P$3") (pinfunction "P$1_P$3") (pintype "bidirectional"))
      (node (ref "U$81") (pin "P$4") (pinfunction "P$1_P$4") (pintype "bidirectional"))
      (node (ref "U$81") (pin "P$5") (pinfunction "P$1_P$5") (pintype "bidirectional"))
      (node (ref "U$81") (pin "P$6") (pinfunction "P$1_P$6") (pintype "bidirectional"))
      (node (ref "U$81") (pin "P$7") (pinfunction "P$1_P$7") (pintype "bidirectional"))
    )
    (net (code "63") (name "Net-(U$82-P$1-PadP$2)") (class "Default")
      (node (ref "U$82") (pin "P$1") (pinfunction "P$1_P$1") (pintype "bidirectional"))
      (node (ref "U$82") (pin "P$2") (pinfunction "P$1_P$2") (pintype "bidirectional"))
      (node (ref "U$82") (pin "P$3") (pinfunction "P$1_P$3") (pintype "bidirectional"))
      (node (ref "U$82") (pin "P$4") (pinfunction "P$1_P$4") (pintype "bidirectional"))
      (node (ref "U$82") (pin "P$5") (pinfunction "P$1_P$5") (pintype "bidirectional"))
      (node (ref "U$82") (pin "P$6") (pinfunction "P$1_P$6") (pintype "bidirectional"))
      (node (ref "U$82") (pin "P$7") (pinfunction "P$1_P$7") (pintype "bidirectional"))
    )
    (net (code "64") (name "Net-(U$83-P$1-PadP$2)") (class "Default")
      (node (ref "U$83") (pin "P$1") (pinfunction "P$1_P$1") (pintype "bidirectional"))
      (node (ref "U$83") (pin "P$2") (pinfunction "P$1_P$2") (pintype "bidirectional"))
      (node (ref "U$83") (pin "P$3") (pinfunction "P$1_P$3") (pintype "bidirectional"))
      (node (ref "U$83") (pin "P$4") (pinfunction "P$1_P$4") (pintype "bidirectional"))
      (node (ref "U$83") (pin "P$5") (pinfunction "P$1_P$5") (pintype "bidirectional"))
      (node (ref "U$83") (pin "P$6") (pinfunction "P$1_P$6") (pintype "bidirectional"))
      (node (ref "U$83") (pin "P$7") (pinfunction "P$1_P$7") (pintype "bidirectional"))
    )
    (net (code "65") (name "Net-(U$84-P$1-PadP$2)") (class "Default")
      (node (ref "U$84") (pin "P$1") (pinfunction "P$1_P$1") (pintype "bidirectional"))
      (node (ref "U$84") (pin "P$2") (pinfunction "P$1_P$2") (pintype "bidirectional"))
      (node (ref "U$84") (pin "P$3") (pinfunction "P$1_P$3") (pintype "bidirectional"))
      (node (ref "U$84") (pin "P$4") (pinfunction "P$1_P$4") (pintype "bidirectional"))
      (node (ref "U$84") (pin "P$5") (pinfunction "P$1_P$5") (pintype "bidirectional"))
      (node (ref "U$84") (pin "P$6") (pinfunction "P$1_P$6") (pintype "bidirectional"))
      (node (ref "U$84") (pin "P$7") (pinfunction "P$1_P$7") (pintype "bidirectional"))
    )
    (net (code "66") (name "Net-(U$85-P$1-PadP$2)") (class "Default")
      (node (ref "U$85") (pin "P$1") (pinfunction "P$1_P$1") (pintype "bidirectional"))
      (node (ref "U$85") (pin "P$2") (pinfunction "P$1_P$2") (pintype "bidirectional"))
      (node (ref "U$85") (pin "P$3") (pinfunction "P$1_P$3") (pintype "bidirectional"))
      (node (ref "U$85") (pin "P$4") (pinfunction "P$1_P$4") (pintype "bidirectional"))
      (node (ref "U$85") (pin "P$5") (pinfunction "P$1_P$5") (pintype "bidirectional"))
      (node (ref "U$85") (pin "P$6") (pinfunction "P$1_P$6") (pintype "bidirectional"))
      (node (ref "U$85") (pin "P$7") (pinfunction "P$1_P$7") (pintype "bidirectional"))
    )
    (net (code "67") (name "Net-(U$86-P$1-PadP$2)") (class "Default")
      (node (ref "U$86") (pin "P$1") (pinfunction "P$1_P$1") (pintype "bidirectional"))
      (node (ref "U$86") (pin "P$2") (pinfunction "P$1_P$2") (pintype "bidirectional"))
      (node (ref "U$86") (pin "P$3") (pinfunction "P$1_P$3") (pintype "bidirectional"))
      (node (ref "U$86") (pin "P$4") (pinfunction "P$1_P$4") (pintype "bidirectional"))
      (node (ref "U$86") (pin "P$5") (pinfunction "P$1_P$5") (pintype "bidirectional"))
      (node (ref "U$86") (pin "P$6") (pinfunction "P$1_P$6") (pintype "bidirectional"))
      (node (ref "U$86") (pin "P$7") (pinfunction "P$1_P$7") (pintype "bidirectional"))
    )
    (net (code "68") (name "Net-(U$87-P$1-PadP$2)") (class "Default")
      (node (ref "U$87") (pin "P$1") (pinfunction "P$1_P$1") (pintype "bidirectional"))
      (node (ref "U$87") (pin "P$2") (pinfunction "P$1_P$2") (pintype "bidirectional"))
      (node (ref "U$87") (pin "P$3") (pinfunction "P$1_P$3") (pintype "bidirectional"))
      (node (ref "U$87") (pin "P$4") (pinfunction "P$1_P$4") (pintype "bidirectional"))
      (node (ref "U$87") (pin "P$5") (pinfunction "P$1_P$5") (pintype "bidirectional"))
      (node (ref "U$87") (pin "P$6") (pinfunction "P$1_P$6") (pintype "bidirectional"))
      (node (ref "U$87") (pin "P$7") (pinfunction "P$1_P$7") (pintype "bidirectional"))
    )
    (net (code "69") (name "Net-(U$88-P$1-PadP$2)") (class "Default")
      (node (ref "U$88") (pin "P$1") (pinfunction "P$1_P$1") (pintype "bidirectional"))
      (node (ref "U$88") (pin "P$2") (pinfunction "P$1_P$2") (pintype "bidirectional"))
      (node (ref "U$88") (pin "P$3") (pinfunction "P$1_P$3") (pintype "bidirectional"))
      (node (ref "U$88") (pin "P$4") (pinfunction "P$1_P$4") (pintype "bidirectional"))
      (node (ref "U$88") (pin "P$5") (pinfunction "P$1_P$5") (pintype "bidirectional"))
      (node (ref "U$88") (pin "P$6") (pinfunction "P$1_P$6") (pintype "bidirectional"))
      (node (ref "U$88") (pin "P$7") (pinfunction "P$1_P$7") (pintype "bidirectional"))
    )
    (net (code "70") (name "Net-(U$89-P$1-PadP$2)") (class "Default")
      (node (ref "U$89") (pin "P$1") (pinfunction "P$1_P$1") (pintype "bidirectional"))
      (node (ref "U$89") (pin "P$2") (pinfunction "P$1_P$2") (pintype "bidirectional"))
      (node (ref "U$89") (pin "P$3") (pinfunction "P$1_P$3") (pintype "bidirectional"))
      (node (ref "U$89") (pin "P$4") (pinfunction "P$1_P$4") (pintype "bidirectional"))
      (node (ref "U$89") (pin "P$5") (pinfunction "P$1_P$5") (pintype "bidirectional"))
      (node (ref "U$89") (pin "P$6") (pinfunction "P$1_P$6") (pintype "bidirectional"))
      (node (ref "U$89") (pin "P$7") (pinfunction "P$1_P$7") (pintype "bidirectional"))
    )
    (net (code "71") (name "Net-(U$90-P$1-PadP$2)") (class "Default")
      (node (ref "U$90") (pin "P$1") (pinfunction "P$1_P$1") (pintype "bidirectional"))
      (node (ref "U$90") (pin "P$2") (pinfunction "P$1_P$2") (pintype "bidirectional"))
      (node (ref "U$90") (pin "P$3") (pinfunction "P$1_P$3") (pintype "bidirectional"))
      (node (ref "U$90") (pin "P$4") (pinfunction "P$1_P$4") (pintype "bidirectional"))
      (node (ref "U$90") (pin "P$5") (pinfunction "P$1_P$5") (pintype "bidirectional"))
      (node (ref "U$90") (pin "P$6") (pinfunction "P$1_P$6") (pintype "bidirectional"))
      (node (ref "U$90") (pin "P$7") (pinfunction "P$1_P$7") (pintype "bidirectional"))
    )
    (net (code "72") (name "Net-(U$91-P$1-PadP$2)") (class "Default")
      (node (ref "U$91") (pin "P$1") (pinfunction "P$1_P$1") (pintype "bidirectional"))
      (node (ref "U$91") (pin "P$2") (pinfunction "P$1_P$2") (pintype "bidirectional"))
      (node (ref "U$91") (pin "P$3") (pinfunction "P$1_P$3") (pintype "bidirectional"))
      (node (ref "U$91") (pin "P$4") (pinfunction "P$1_P$4") (pintype "bidirectional"))
      (node (ref "U$91") (pin "P$5") (pinfunction "P$1_P$5") (pintype "bidirectional"))
      (node (ref "U$91") (pin "P$6") (pinfunction "P$1_P$6") (pintype "bidirectional"))
      (node (ref "U$91") (pin "P$7") (pinfunction "P$1_P$7") (pintype "bidirectional"))
    )
    (net (code "73") (name "Net-(U$92-P$1-PadP$2)") (class "Default")
      (node (ref "U$92") (pin "P$1") (pinfunction "P$1_P$1") (pintype "bidirectional"))
      (node (ref "U$92") (pin "P$2") (pinfunction "P$1_P$2") (pintype "bidirectional"))
      (node (ref "U$92") (pin "P$3") (pinfunction "P$1_P$3") (pintype "bidirectional"))
      (node (ref "U$92") (pin "P$4") (pinfunction "P$1_P$4") (pintype "bidirectional"))
      (node (ref "U$92") (pin "P$5") (pinfunction "P$1_P$5") (pintype "bidirectional"))
      (node (ref "U$92") (pin "P$6") (pinfunction "P$1_P$6") (pintype "bidirectional"))
      (node (ref "U$92") (pin "P$7") (pinfunction "P$1_P$7") (pintype "bidirectional"))
    )
    (net (code "74") (name "Net-(U$93-P$1-PadP$2)") (class "Default")
      (node (ref "U$93") (pin "P$1") (pinfunction "P$1_P$1") (pintype "bidirectional"))
      (node (ref "U$93") (pin "P$2") (pinfunction "P$1_P$2") (pintype "bidirectional"))
      (node (ref "U$93") (pin "P$3") (pinfunction "P$1_P$3") (pintype "bidirectional"))
      (node (ref "U$93") (pin "P$4") (pinfunction "P$1_P$4") (pintype "bidirectional"))
      (node (ref "U$93") (pin "P$5") (pinfunction "P$1_P$5") (pintype "bidirectional"))
      (node (ref "U$93") (pin "P$6") (pinfunction "P$1_P$6") (pintype "bidirectional"))
      (node (ref "U$93") (pin "P$7") (pinfunction "P$1_P$7") (pintype "bidirectional"))
    )
  )
)
